# Sheet1.net
KiCad netlist of a schematic drawn in Altium Designer
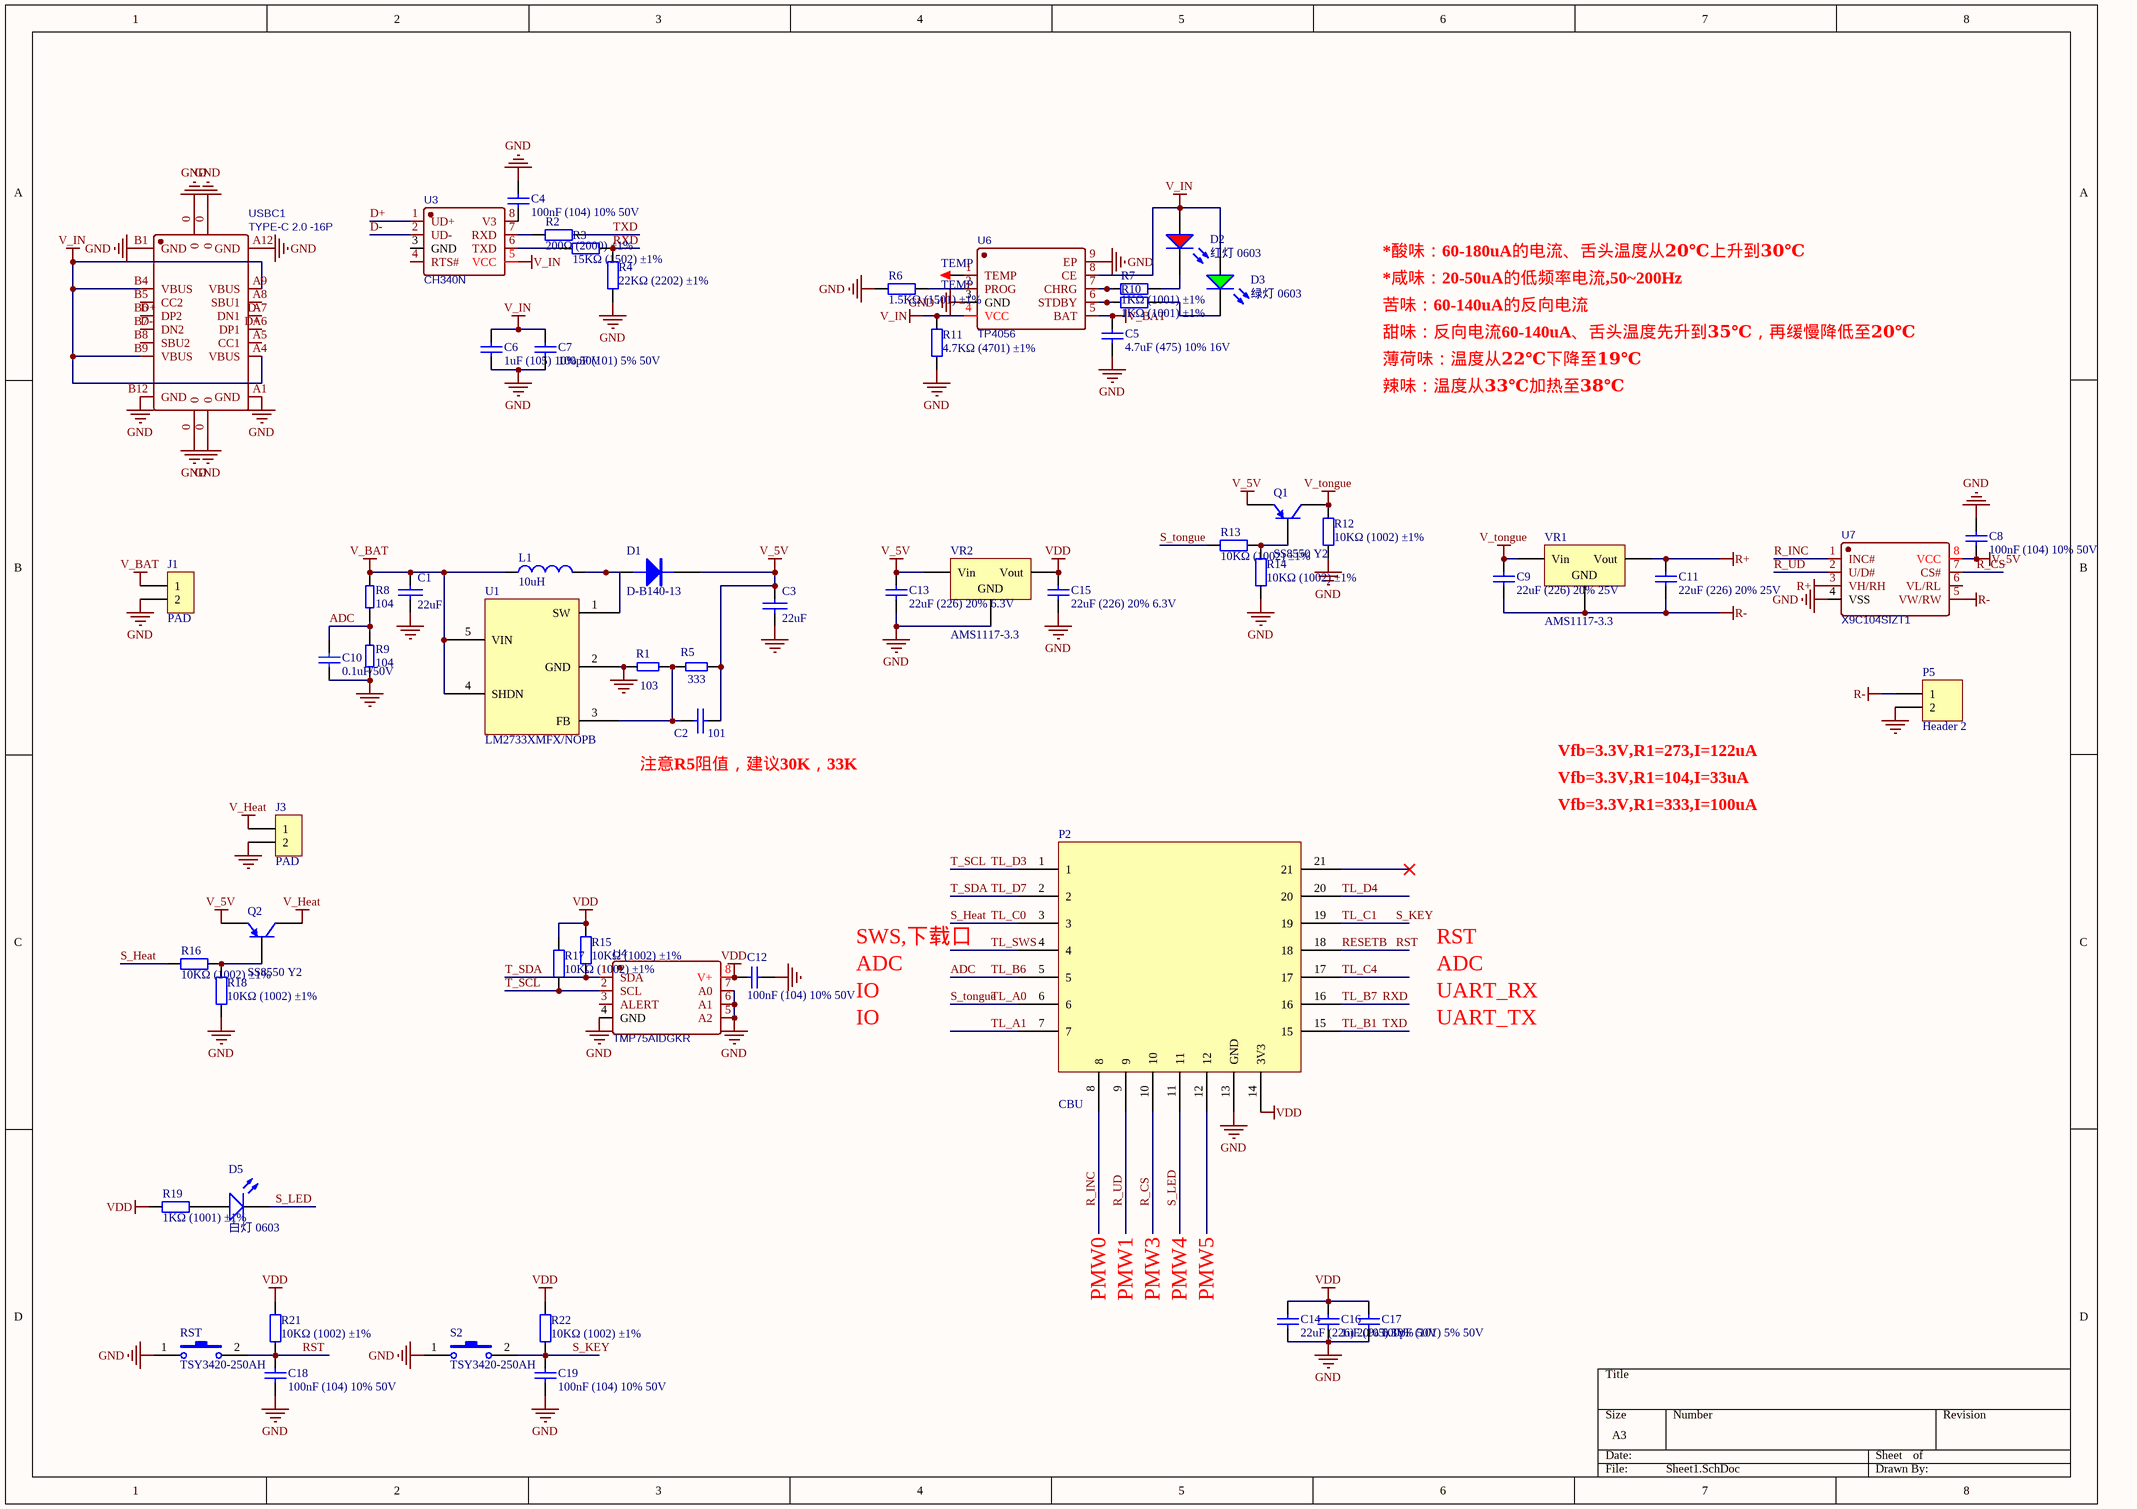
[diagram p0: Sheet1.SchDoc]

(export (version "E")
  (design (tool "Eeschema 10.0.6"))
  (components
    (comp (ref "C1") (value "22uF") (footprint "C1206") (libsource (lib "altium-import") (part "root_0_C1_")))
    (comp (ref "C2")
      (value "101")
      (footprint "C0603")
      (description "Capacitor")
      (libsource (lib "先锋器件封装库") (part "CAP"))
    )
    (comp (ref "C3") (value "22uF") (footprint "C1206") (libsource (lib "altium-import") (part "root_0_C1_")))
    (comp (ref "C4")
      (value "100nF (104) 10% 50V")
      (footprint "0603_C")
      (description "贴片电容")
      (libsource (lib "Miscellaneous Devices LC") (part "0603 100nF (104) 10% 50V"))
    )
    (comp (ref "C5")
      (value "4.7uF (475) 10% 16V")
      (footprint "0603_C")
      (description "贴片电容")
      (libsource (lib "Miscellaneous Devices LC") (part "0603 4.7uF (475) 10% 16V"))
    )
    (comp (ref "C6")
      (value "1uF (105) 10% 50V")
      (footprint "0603_C")
      (description "贴片电容")
      (libsource (lib "Miscellaneous Devices LC") (part "0603 1uF (105) 10% 50V"))
    )
    (comp (ref "C7")
      (value "100pF (101) 5% 50V")
      (footprint "0603_C")
      (description "贴片电容")
      (libsource (lib "Miscellaneous Devices LC") (part "0603 100pF (101) 5% 50V"))
    )
    (comp (ref "C8")
      (value "100nF (104) 10% 50V")
      (footprint "0603_C")
      (description "贴片电容")
      (libsource (lib "Miscellaneous Devices LC") (part "0603 100nF (104) 10% 50V"))
    )
    (comp (ref "C9")
      (value "22uF (226) 20% 25V")
      (footprint "0805_C")
      (description "贴片电容")
      (libsource (lib "Miscellaneous Devices LC") (part "0805 22uF (226) 20% 25V"))
    )
    (comp (ref "C10")
      (value "0.1uF/50V")
      (footprint "C0603_GRM18")
      (description "无极性电容")
      (fields (field (name "PART NUMBER") "1.02.05.00150") (field (name "修改人") "system"))
      (libsource (lib "Database_Libs") (part "Capacitor - non polarized"))
    )
    (comp (ref "C11")
      (value "22uF (226) 20% 25V")
      (footprint "0805_C")
      (description "贴片电容")
      (libsource (lib "Miscellaneous Devices LC") (part "0805 22uF (226) 20% 25V"))
    )
    (comp (ref "C12")
      (value "100nF (104) 10% 50V")
      (footprint "0603_C")
      (description "贴片电容")
      (libsource (lib "Miscellaneous Devices LC") (part "0603 100nF (104) 10% 50V"))
    )
    (comp (ref "C13")
      (value "22uF (226) 20% 6.3V")
      (footprint "0603_C")
      (description "贴片电容")
      (libsource (lib "Miscellaneous Devices LC") (part "0603 22uF (226) 20% 6.3V"))
    )
    (comp (ref "C14")
      (value "22uF (226) 20% 6.3V")
      (footprint "0603_C")
      (description "贴片电容")
      (libsource (lib "Miscellaneous Devices LC") (part "0603 22uF (226) 20% 6.3V"))
    )
    (comp (ref "C15")
      (value "22uF (226) 20% 6.3V")
      (footprint "0603_C")
      (description "贴片电容")
      (libsource (lib "Miscellaneous Devices LC") (part "0603 22uF (226) 20% 6.3V"))
    )
    (comp (ref "C16")
      (value "1uF (105) 10% 50V")
      (footprint "0603_C")
      (description "贴片电容")
      (libsource (lib "Miscellaneous Devices LC") (part "0603 1uF (105) 10% 50V"))
    )
    (comp (ref "C17")
      (value "100pF (101) 5% 50V")
      (footprint "0603_C")
      (description "贴片电容")
      (libsource (lib "Miscellaneous Devices LC") (part "0603 100pF (101) 5% 50V"))
    )
    (comp (ref "C18")
      (value "100nF (104) 10% 50V")
      (footprint "0603_C")
      (description "贴片电容")
      (libsource (lib "Miscellaneous Devices LC") (part "0603 100nF (104) 10% 50V"))
    )
    (comp (ref "C19")
      (value "100nF (104) 10% 50V")
      (footprint "0603_C")
      (description "贴片电容")
      (libsource (lib "Miscellaneous Devices LC") (part "0603 100nF (104) 10% 50V"))
    )
    (comp (ref "D1")
      (value "D-B140-13")
      (footprint "XF-SS12C")
      (description "Diode")
      (fields (field (name "SPECIFICATION") "D-B140-13"))
      (libsource (lib "先锋器件封装库") (part "DIODE"))
    )
    (comp (ref "D2")
      (value "红灯 0603")
      (footprint "0603_LED_S1")
      (description "发光二极管")
      (libsource (lib "LED") (part "0603 红灯"))
    )
    (comp (ref "D3")
      (value "绿灯 0603")
      (footprint "0603_LED_S1")
      (description "发光二极管")
      (libsource (lib "LED") (part "0603 绿灯"))
    )
    (comp (ref "D5")
      (value "白灯 0603")
      (footprint "0603_LED_S1")
      (description "发光二极管")
      (libsource (lib "LED") (part "0603 白灯"))
    )
    (comp (ref "J1")
      (value "PAD")
      (footprint "POW_5#")
      (description "Connector")
      (libsource (lib "altium-import") (part "root_0_CON2_"))
    )
    (comp (ref "J3")
      (value "PAD")
      (footprint "HDR1X2")
      (description "Connector")
      (libsource (lib "接插件") (part "CON2"))
    )
    (comp (ref "L1")
      (value "10uH")
      (footprint "CD73")
      (description "Inductor")
      (fields (field (name "Comment") "4.7uH") (field (name "PUBLISHER") "Altium Limited"))
      (libsource (lib "altium-import") (part "root_0_Inductor_"))
    )
    (comp (ref "P2")
      (value "CBU")
      (footprint "CBU-PCBA")
      (fields (field (name "PART NUMBER") "0110"))
      (libsource (lib "Database_Libs1") (part "CBU"))
    )
    (comp (ref "P5")
      (value "Header 2")
      (footprint "HDR1X2")
      (description "Header, 2-Pin")
      (fields (field (name "PUBLISHER") "Altium Limited"))
      (libsource (lib "Miscellaneous Connectors") (part "Header 2"))
    )
    (comp (ref "Q1")
      (value "SS8550 Y2")
      (footprint "SOT-23(SOT-23-3)")
      (description "三极管")
      (libsource (lib "Transistor_PNP") (part "SOT-23 SS8550 Y2"))
    )
    (comp (ref "Q2")
      (value "SS8550 Y2")
      (footprint "SOT-23(SOT-23-3)")
      (description "三极管")
      (libsource (lib "Transistor_PNP") (part "SOT-23 SS8550 Y2"))
    )
    (comp (ref "R1")
      (value "103")
      (footprint "R0603")
      (description "RES")
      (libsource (lib "先锋器件封装库") (part "RES-1"))
    )
    (comp (ref "R2")
      (value "200Ω (2000) ±1%")
      (footprint "0603_R")
      (description "贴片电阻")
      (libsource (lib "Miscellaneous Devices LC") (part "0603 200Ω (2000) 1%"))
    )
    (comp (ref "R3")
      (value "15KΩ (1502) ±1%")
      (footprint "0603_R")
      (description "贴片电阻")
      (libsource (lib "Miscellaneous Devices LC") (part "0603 15KΩ (1502) 1%"))
    )
    (comp (ref "R4")
      (value "22KΩ (2202) ±1%")
      (footprint "0603_R")
      (description "贴片电阻")
      (libsource (lib "Miscellaneous Devices LC") (part "0603 22KΩ (2202) 1%"))
    )
    (comp (ref "R5")
      (value "333")
      (footprint "R0603")
      (description "RES")
      (libsource (lib "先锋器件封装库") (part "RES-1"))
    )
    (comp (ref "R6")
      (value "1.5KΩ (1501) ±1%")
      (footprint "0603_R")
      (description "贴片电阻")
      (libsource (lib "Miscellaneous Devices LC") (part "0603 1.5KΩ (1501) 1%"))
    )
    (comp (ref "R7")
      (value "1KΩ (1001) ±1%")
      (footprint "0603_R")
      (description "贴片电阻")
      (libsource (lib "Miscellaneous Devices LC") (part "0603 1KΩ (1001) 1%"))
    )
    (comp (ref "R8")
      (value "104")
      (footprint "R0603")
      (description "RES")
      (libsource (lib "先锋器件封装库") (part "RES-1"))
    )
    (comp (ref "R9")
      (value "104")
      (footprint "R0603")
      (description "RES")
      (libsource (lib "先锋器件封装库") (part "RES-1"))
    )
    (comp (ref "R10")
      (value "1KΩ (1001) ±1%")
      (footprint "0603_R")
      (description "贴片电阻")
      (libsource (lib "Miscellaneous Devices LC") (part "0603 1KΩ (1001) 1%"))
    )
    (comp (ref "R11")
      (value "4.7KΩ (4701) ±1%")
      (footprint "0603_R")
      (description "贴片电阻")
      (libsource (lib "Miscellaneous Devices LC") (part "0603 4.7KΩ (4701) 1%"))
    )
    (comp (ref "R12")
      (value "10KΩ (1002) ±1%")
      (footprint "0603_R")
      (description "贴片电阻")
      (libsource (lib "Miscellaneous Devices LC") (part "0603 10KΩ (1002) 1%"))
    )
    (comp (ref "R13")
      (value "10KΩ (1002) ±1%")
      (footprint "0603_R")
      (description "贴片电阻")
      (libsource (lib "") (part "0603 10KΩ (1002) 1%_3"))
    )
    (comp (ref "R14")
      (value "10KΩ (1002) ±1%")
      (footprint "0603_R")
      (description "贴片电阻")
      (libsource (lib "") (part "0603 10KΩ (1002) 1%_2"))
    )
    (comp (ref "R15")
      (value "10KΩ (1002) ±1%")
      (footprint "0603_R")
      (description "贴片电阻")
      (libsource (lib "Miscellaneous Devices LC") (part "0603 10KΩ (1002) 1%"))
    )
    (comp (ref "R16")
      (value "10KΩ (1002) ±1%")
      (footprint "0603_R")
      (description "贴片电阻")
      (libsource (lib "") (part "0603 10KΩ (1002) 1%_1"))
    )
    (comp (ref "R17")
      (value "10KΩ (1002) ±1%")
      (footprint "0603_R")
      (description "贴片电阻")
      (libsource (lib "Miscellaneous Devices LC") (part "0603 10KΩ (1002) 1%"))
    )
    (comp (ref "R18")
      (value "10KΩ (1002) ±1%")
      (footprint "0603_R")
      (description "贴片电阻")
      (libsource (lib "Miscellaneous Devices LC") (part "0603 10KΩ (1002) 1%"))
    )
    (comp (ref "R19")
      (value "1KΩ (1001) ±1%")
      (footprint "0603_R")
      (description "贴片电阻")
      (libsource (lib "Miscellaneous Devices LC") (part "0603 1KΩ (1001) 1%"))
    )
    (comp (ref "R21")
      (value "10KΩ (1002) ±1%")
      (footprint "0603_R")
      (description "贴片电阻")
      (libsource (lib "Miscellaneous Devices LC") (part "0603 10KΩ (1002) 1%"))
    )
    (comp (ref "R22")
      (value "10KΩ (1002) ±1%")
      (footprint "0603_R")
      (description "贴片电阻")
      (libsource (lib "Miscellaneous Devices LC") (part "0603 10KΩ (1002) 1%"))
    )
    (comp (ref "RST")
      (value "TSY3420-250AH")
      (footprint "TSW SMD-3*6*4.3")
      (description "2pin轻触开关（无固定脚）")
      (fields (field (name "PART NUMBER") "1.13.04.00024") (field (name "修改人") "system"))
      (libsource (lib "Database_Libs") (part "SW-PB2"))
    )
    (comp (ref "S2")
      (value "TSY3420-250AH")
      (footprint "TSW SMD-3*6*4.3")
      (description "2pin轻触开关（无固定脚）")
      (fields (field (name "PART NUMBER") "1.13.04.00024") (field (name "修改人") "system"))
      (libsource (lib "Database_Libs") (part "SW-PB2"))
    )
    (comp (ref "TEMP")
      (value "TEMP")
      (footprint "TEST 1")
      (description "测试点")
      (libsource (lib "0.7 - 常用按键-开关-蜂鸣器-电池") (part "TEST"))
    )
    (comp (ref "U1")
      (value "LM2733XMFX/NOPB")
      (footprint "SOT23-5")
      (description "LM2733")
      (fields (field (name "SPECIFICATION") "LM2733XMFX/NOPB"))
      (libsource (lib "先锋器件封装库") (part "LM2733"))
    )
    (comp (ref "U3")
      (value "CH340N")
      (footprint "SOP-8")
      (fields (field (name "BOM_SUPPLIER PART") "C506813") (field (name "CONTRIBUTOR") "LCSC"))
      (libsource (lib "TY") (part "CH340N"))
    )
    (comp (ref "U4")
      (value "TMP75AIDGKR")
      (footprint "VSSOP-8_L3.0-W3.0-P0.65-LS5.0-BL")
      (fields (field (name "BOM_SUPPLIER PART") "C105258") (field (name "CONTRIBUTOR") "LCSC"))
      (libsource (lib "TY") (part "TMP75AIDGKR"))
    )
    (comp (ref "U6")
      (value "TP4056")
      (footprint "ESOP8_N")
      (fields (field (name "BOM_SUPPLIER PART") "C725790") (field (name "CONTRIBUTOR") "LCSC"))
      (libsource (lib "TY") (part "TP4056_C725790"))
    )
    (comp (ref "U7")
      (value "X9C104SIZT1")
      (footprint "SOIC-8")
      (fields (field (name "BOM_SUPPLIER PART") "C11979"))
      (libsource (lib "TY") (part "X9C104SIZT1"))
    )
    (comp (ref "USBC1")
      (value "TYPE-C 2.0 -16P")
      (footprint "USB-C-SMD_TYPE-C-USB-5")
      (description "USB2.0 Type-C 母座 16Pin")
      (libsource (lib "0.8 - 以太网-音频-USB插座") (part "USB2.0 Type-C 16Pin母座"))
    )
    (comp (ref "VR1")
      (value "AMS1117-3.3")
      (footprint "SOT-223")
      (description "低压差线性稳压(LDO)")
      (libsource (lib "LDO") (part "SOT-223 AMS1117-3.3"))
    )
    (comp (ref "VR2")
      (value "AMS1117-3.3")
      (footprint "SOT-223")
      (description "低压差线性稳压(LDO)")
      (libsource (lib "LDO") (part "SOT-223 AMS1117-3.3"))
    )
  )
  (nets
    (net (code "1") (name "/ADC") (class "Default")
      (node (ref "C10") (pin "2") (pinfunction "2_2") (pintype "passive"))
      (node (ref "P2") (pin "5") (pinfunction "5_5") (pintype "passive"))
      (node (ref "R8") (pin "1") (pintype "passive"))
      (node (ref "R9") (pin "2") (pintype "passive"))
    )
    (net (code "2") (name "/D+") (class "Default")
      (node (ref "U3") (pin "1") (pinfunction "UD+_1") (pintype "passive"))
      (node (ref "USBC1") (pin "A6") (pinfunction "DP1_A6") (pintype "passive"))
      (node (ref "USBC1") (pin "B6") (pinfunction "DP2_B6") (pintype "passive"))
    )
    (net (code "3") (name "/D-") (class "Default")
      (node (ref "U3") (pin "2") (pinfunction "UD-_2") (pintype "passive"))
      (node (ref "USBC1") (pin "A7") (pinfunction "DN1_A7") (pintype "passive"))
      (node (ref "USBC1") (pin "B7") (pinfunction "DN2_B7") (pintype "passive"))
    )
    (net (code "4") (name "/RESETB") (class "Default")
      (node (ref "C18") (pin "2") (pinfunction "2_2") (pintype "passive"))
      (node (ref "P2") (pin "18") (pinfunction "18_18") (pintype "passive"))
      (node (ref "R21") (pin "1") (pinfunction "1_1") (pintype "passive"))
      (node (ref "RST") (pin "2") (pinfunction "2_2") (pintype "passive"))
    )
    (net (code "5") (name "/RXD") (class "Default")
      (node (ref "P2") (pin "16") (pinfunction "16_16") (pintype "passive"))
      (node (ref "R3") (pin "2") (pinfunction "2_2") (pintype "passive"))
      (node (ref "R4") (pin "2") (pinfunction "2_2") (pintype "passive"))
    )
    (net (code "6") (name "/R_CS") (class "Default")
      (node (ref "P2") (pin "10") (pinfunction "10_10") (pintype "passive"))
      (node (ref "U7") (pin "7") (pinfunction "CS#_7") (pintype "passive"))
    )
    (net (code "7") (name "/R_INC") (class "Default")
      (node (ref "P2") (pin "8") (pinfunction "8_8") (pintype "passive"))
      (node (ref "U7") (pin "1") (pinfunction "INC#_1") (pintype "passive"))
    )
    (net (code "8") (name "/R_UD") (class "Default")
      (node (ref "P2") (pin "9") (pinfunction "9_9") (pintype "passive"))
      (node (ref "U7") (pin "2") (pinfunction "U/D#_2") (pintype "passive"))
    )
    (net (code "9") (name "/S_Heat") (class "Default")
      (node (ref "P2") (pin "3") (pinfunction "3_3") (pintype "passive"))
      (node (ref "R16") (pin "1") (pinfunction "1_1") (pintype "passive"))
    )
    (net (code "10") (name "/S_KEY") (class "Default")
      (node (ref "C19") (pin "2") (pinfunction "2_2") (pintype "passive"))
      (node (ref "P2") (pin "19") (pinfunction "19_19") (pintype "passive"))
      (node (ref "R22") (pin "1") (pinfunction "1_1") (pintype "passive"))
      (node (ref "S2") (pin "2") (pinfunction "2_2") (pintype "passive"))
    )
    (net (code "11") (name "/S_LED") (class "Default")
      (node (ref "D5") (pin "K") (pinfunction "K_K") (pintype "passive"))
      (node (ref "P2") (pin "11") (pinfunction "11_11") (pintype "passive"))
    )
    (net (code "12") (name "/S_tongue") (class "Default")
      (node (ref "P2") (pin "6") (pinfunction "6_6") (pintype "passive"))
      (node (ref "R13") (pin "2") (pinfunction "2_2") (pintype "passive"))
    )
    (net (code "13") (name "/TL_A1") (class "Default")
      (node (ref "P2") (pin "7") (pinfunction "7_7") (pintype "passive"))
    )
    (net (code "14") (name "/TL_B1") (class "Default")
      (node (ref "P2") (pin "15") (pinfunction "15_15") (pintype "passive"))
      (node (ref "R2") (pin "2") (pinfunction "2_2") (pintype "passive"))
    )
    (net (code "15") (name "/TL_C4") (class "Default")
      (node (ref "P2") (pin "17") (pinfunction "17_17") (pintype "passive"))
    )
    (net (code "16") (name "/TL_D3") (class "Default")
      (node (ref "P2") (pin "1") (pinfunction "1_1") (pintype "passive"))
      (node (ref "R17") (pin "1") (pinfunction "1_1") (pintype "passive"))
      (node (ref "U4") (pin "2") (pinfunction "SCL_2") (pintype "passive"))
    )
    (net (code "17") (name "/TL_D4") (class "Default")
      (node (ref "P2") (pin "20") (pinfunction "20_20") (pintype "passive"))
    )
    (net (code "18") (name "/TL_D7") (class "Default")
      (node (ref "P2") (pin "2") (pinfunction "2_2") (pintype "passive"))
      (node (ref "R15") (pin "1") (pinfunction "1_1") (pintype "passive"))
      (node (ref "U4") (pin "1") (pinfunction "SDA_1") (pintype "passive"))
    )
    (net (code "19") (name "/TL_SWS") (class "Default")
      (node (ref "P2") (pin "4") (pinfunction "4_4") (pintype "passive"))
    )
    (net (code "20") (name "GND") (class "Default")
      (node (ref "C1") (pin "2") (pinfunction "2_2") (pintype "passive"))
      (node (ref "C10") (pin "1") (pinfunction "1_1") (pintype "passive"))
      (node (ref "C12") (pin "2") (pinfunction "2_2") (pintype "passive"))
      (node (ref "C13") (pin "1") (pinfunction "1_1") (pintype "passive"))
      (node (ref "C14") (pin "1") (pinfunction "1_1") (pintype "passive"))
      (node (ref "C15") (pin "1") (pinfunction "1_1") (pintype "passive"))
      (node (ref "C16") (pin "1") (pinfunction "1_1") (pintype "passive"))
      (node (ref "C17") (pin "1") (pinfunction "1_1") (pintype "passive"))
      (node (ref "C18") (pin "1") (pinfunction "1_1") (pintype "passive"))
      (node (ref "C19") (pin "1") (pinfunction "1_1") (pintype "passive"))
      (node (ref "C3") (pin "2") (pinfunction "2_2") (pintype "passive"))
      (node (ref "C4") (pin "2") (pinfunction "2_2") (pintype "passive"))
      (node (ref "C5") (pin "1") (pinfunction "1_1") (pintype "passive"))
      (node (ref "C6") (pin "1") (pinfunction "1_1") (pintype "passive"))
      (node (ref "C7") (pin "1") (pinfunction "1_1") (pintype "passive"))
      (node (ref "C8") (pin "2") (pinfunction "2_2") (pintype "passive"))
      (node (ref "J1") (pin "2") (pinfunction "2_2") (pintype "passive"))
      (node (ref "J3") (pin "2") (pinfunction "2_2") (pintype "passive"))
      (node (ref "P2") (pin "13") (pinfunction "GND_13") (pintype "passive"))
      (node (ref "P5") (pin "2") (pinfunction "2_2") (pintype "passive"))
      (node (ref "R1") (pin "1") (pintype "passive"))
      (node (ref "R11") (pin "1") (pinfunction "1_1") (pintype "passive"))
      (node (ref "R12") (pin "1") (pinfunction "1_1") (pintype "passive"))
      (node (ref "R14") (pin "2") (pinfunction "2_2") (pintype "passive"))
      (node (ref "R18") (pin "1") (pinfunction "1_1") (pintype "passive"))
      (node (ref "R4") (pin "1") (pinfunction "1_1") (pintype "passive"))
      (node (ref "R6") (pin "1") (pinfunction "1_1") (pintype "passive"))
      (node (ref "R9") (pin "1") (pintype "passive"))
      (node (ref "RST") (pin "1") (pinfunction "1_1") (pintype "passive"))
      (node (ref "S2") (pin "1") (pinfunction "1_1") (pintype "passive"))
      (node (ref "U1") (pin "2") (pinfunction "GND_2") (pintype "passive"))
      (node (ref "U4") (pin "4") (pinfunction "GND_4") (pintype "passive"))
      (node (ref "U4") (pin "5") (pinfunction "A2_5") (pintype "passive"))
      (node (ref "U4") (pin "6") (pinfunction "A1_6") (pintype "passive"))
      (node (ref "U4") (pin "7") (pinfunction "A0_7") (pintype "passive"))
      (node (ref "U6") (pin "3") (pinfunction "GND_3") (pintype "passive"))
      (node (ref "U6") (pin "9") (pinfunction "EP_9") (pintype "passive"))
      (node (ref "U7") (pin "4") (pinfunction "VSS_4") (pintype "passive"))
      (node (ref "USBC1") (pin "0") (pinfunction "0_0") (pintype "passive"))
      (node (ref "USBC1") (pin "A1") (pinfunction "GND_A1") (pintype "passive"))
      (node (ref "USBC1") (pin "A12") (pinfunction "GND_A12") (pintype "passive"))
      (node (ref "USBC1") (pin "B1") (pinfunction "GND_B1") (pintype "passive"))
      (node (ref "USBC1") (pin "B12") (pinfunction "GND_B12") (pintype "passive"))
      (node (ref "VR2") (pin "1") (pinfunction "GND_1") (pintype "passive"))
    )
    (net (code "21") (name "Net-(D2-PadK)") (class "Default")
      (node (ref "D2") (pin "K") (pinfunction "K_K") (pintype "passive"))
      (node (ref "R7") (pin "2") (pinfunction "2_2") (pintype "passive"))
    )
    (net (code "22") (name "Net-(D3-PadK)") (class "Default")
      (node (ref "D3") (pin "K") (pinfunction "K_K") (pintype "passive"))
      (node (ref "R10") (pin "2") (pinfunction "2_2") (pintype "passive"))
    )
    (net (code "23") (name "Net-(D5-PadA)") (class "Default")
      (node (ref "D5") (pin "A") (pinfunction "A_A") (pintype "passive"))
      (node (ref "R19") (pin "2") (pinfunction "2_2") (pintype "passive"))
    )
    (net (code "24") (name "Net-(Q1-B)") (class "Default")
      (node (ref "Q1") (pin "1") (pinfunction "B_1") (pintype "passive"))
      (node (ref "R13") (pin "1") (pinfunction "1_1") (pintype "passive"))
      (node (ref "R14") (pin "1") (pinfunction "1_1") (pintype "passive"))
    )
    (net (code "25") (name "Net-(Q2-B)") (class "Default")
      (node (ref "Q2") (pin "1") (pinfunction "B_1") (pintype "passive"))
      (node (ref "R16") (pin "2") (pinfunction "2_2") (pintype "passive"))
      (node (ref "R18") (pin "2") (pinfunction "2_2") (pintype "passive"))
    )
    (net (code "26") (name "Net-(U1-FB)") (class "Default")
      (node (ref "C2") (pin "2") (pinfunction "2_2") (pintype "passive"))
      (node (ref "R1") (pin "2") (pintype "passive"))
      (node (ref "R5") (pin "2") (pintype "passive"))
      (node (ref "U1") (pin "3") (pinfunction "FB_3") (pintype "passive"))
    )
    (net (code "27") (name "Net-(U1-SW)") (class "Default")
      (node (ref "D1") (pin "A") (pinfunction "A_A") (pintype "passive"))
      (node (ref "L1") (pin "2") (pinfunction "2_2") (pintype "passive"))
      (node (ref "U1") (pin "1") (pinfunction "SW_1") (pintype "passive"))
    )
    (net (code "28") (name "Net-(U3-RXD)") (class "Default")
      (node (ref "R2") (pin "1") (pinfunction "1_1") (pintype "passive"))
      (node (ref "U3") (pin "7") (pinfunction "RXD_7") (pintype "passive"))
    )
    (net (code "29") (name "Net-(U3-TXD)") (class "Default")
      (node (ref "R3") (pin "1") (pinfunction "1_1") (pintype "passive"))
      (node (ref "U3") (pin "6") (pinfunction "TXD_6") (pintype "passive"))
    )
    (net (code "30") (name "Net-(U3-V3)") (class "Default")
      (node (ref "C4") (pin "1") (pinfunction "1_1") (pintype "passive"))
      (node (ref "U3") (pin "8") (pinfunction "V3_8") (pintype "passive"))
    )
    (net (code "31") (name "Net-(U6-CHRG)") (class "Default")
      (node (ref "R7") (pin "1") (pinfunction "1_1") (pintype "passive"))
      (node (ref "U6") (pin "7") (pinfunction "CHRG_7") (pintype "passive"))
    )
    (net (code "32") (name "Net-(U6-PROG)") (class "Default")
      (node (ref "R6") (pin "2") (pinfunction "2_2") (pintype "passive"))
      (node (ref "U6") (pin "2") (pinfunction "PROG_2") (pintype "passive"))
    )
    (net (code "33") (name "Net-(U6-STDBY)") (class "Default")
      (node (ref "R10") (pin "1") (pinfunction "1_1") (pintype "passive"))
      (node (ref "U6") (pin "6") (pinfunction "STDBY_6") (pintype "passive"))
    )
    (net (code "34") (name "Net-(U6-TEMP)") (class "Default")
      (node (ref "TEMP") (pin "1") (pinfunction "1_1") (pintype "passive"))
      (node (ref "U6") (pin "1") (pinfunction "TEMP_1") (pintype "passive"))
    )
    (net (code "35") (name "R+") (class "Default")
      (node (ref "C11") (pin "2") (pinfunction "2_2") (pintype "passive"))
      (node (ref "U7") (pin "3") (pinfunction "VH/RH_3") (pintype "passive"))
      (node (ref "VR1") (pin "2") (pinfunction "Vout_2") (pintype "passive"))
    )
    (net (code "36") (name "R-") (class "Default")
      (node (ref "C11") (pin "1") (pinfunction "1_1") (pintype "passive"))
      (node (ref "C9") (pin "1") (pinfunction "1_1") (pintype "passive"))
      (node (ref "P5") (pin "1") (pinfunction "1_1") (pintype "passive"))
      (node (ref "U7") (pin "5") (pinfunction "VW/RW_5") (pintype "passive"))
      (node (ref "VR1") (pin "1") (pinfunction "GND_1") (pintype "passive"))
    )
    (net (code "37") (name "VDD") (class "Default")
      (node (ref "C12") (pin "1") (pinfunction "1_1") (pintype "passive"))
      (node (ref "C14") (pin "2") (pinfunction "2_2") (pintype "passive"))
      (node (ref "C15") (pin "2") (pinfunction "2_2") (pintype "passive"))
      (node (ref "C16") (pin "2") (pinfunction "2_2") (pintype "passive"))
      (node (ref "C17") (pin "2") (pinfunction "2_2") (pintype "passive"))
      (node (ref "P2") (pin "14") (pinfunction "3V3_14") (pintype "passive"))
      (node (ref "R15") (pin "2") (pinfunction "2_2") (pintype "passive"))
      (node (ref "R17") (pin "2") (pinfunction "2_2") (pintype "passive"))
      (node (ref "R19") (pin "1") (pinfunction "1_1") (pintype "passive"))
      (node (ref "R21") (pin "2") (pinfunction "2_2") (pintype "passive"))
      (node (ref "R22") (pin "2") (pinfunction "2_2") (pintype "passive"))
      (node (ref "U4") (pin "8") (pinfunction "V+_8") (pintype "passive"))
      (node (ref "VR2") (pin "2") (pinfunction "Vout_2") (pintype "passive"))
    )
    (net (code "38") (name "V_5V") (class "Default")
      (node (ref "C13") (pin "2") (pinfunction "2_2") (pintype "passive"))
      (node (ref "C2") (pin "1") (pinfunction "1_1") (pintype "passive"))
      (node (ref "C3") (pin "1") (pinfunction "1_1") (pintype "passive"))
      (node (ref "C8") (pin "1") (pinfunction "1_1") (pintype "passive"))
      (node (ref "D1") (pin "K") (pinfunction "K_K") (pintype "passive"))
      (node (ref "Q1") (pin "2") (pinfunction "E_2") (pintype "passive"))
      (node (ref "Q2") (pin "2") (pinfunction "E_2") (pintype "passive"))
      (node (ref "R5") (pin "1") (pintype "passive"))
      (node (ref "U7") (pin "8") (pinfunction "VCC_8") (pintype "passive"))
      (node (ref "VR2") (pin "3") (pinfunction "Vin_3") (pintype "passive"))
    )
    (net (code "39") (name "V_BAT") (class "Default")
      (node (ref "C1") (pin "1") (pinfunction "1_1") (pintype "passive"))
      (node (ref "C5") (pin "2") (pinfunction "2_2") (pintype "passive"))
      (node (ref "J1") (pin "1") (pinfunction "1_1") (pintype "passive"))
      (node (ref "L1") (pin "1") (pinfunction "1_1") (pintype "passive"))
      (node (ref "R8") (pin "2") (pintype "passive"))
      (node (ref "U1") (pin "4") (pinfunction "SHDN_4") (pintype "passive"))
      (node (ref "U1") (pin "5") (pinfunction "VIN_5") (pintype "passive"))
      (node (ref "U6") (pin "5") (pinfunction "BAT_5") (pintype "passive"))
    )
    (net (code "40") (name "V_Heat") (class "Default")
      (node (ref "J3") (pin "1") (pinfunction "1_1") (pintype "passive"))
      (node (ref "Q2") (pin "3") (pinfunction "C_3") (pintype "passive"))
    )
    (net (code "41") (name "V_IN") (class "Default")
      (node (ref "C6") (pin "2") (pinfunction "2_2") (pintype "passive"))
      (node (ref "C7") (pin "2") (pinfunction "2_2") (pintype "passive"))
      (node (ref "D2") (pin "A") (pinfunction "A_A") (pintype "passive"))
      (node (ref "D3") (pin "A") (pinfunction "A_A") (pintype "passive"))
      (node (ref "R11") (pin "2") (pinfunction "2_2") (pintype "passive"))
      (node (ref "U3") (pin "5") (pinfunction "VCC_5") (pintype "passive"))
      (node (ref "U6") (pin "4") (pinfunction "VCC_4") (pintype "passive"))
      (node (ref "U6") (pin "8") (pinfunction "CE_8") (pintype "passive"))
      (node (ref "USBC1") (pin "A4") (pinfunction "VBUS_A4") (pintype "passive"))
      (node (ref "USBC1") (pin "A9") (pinfunction "VBUS_A9") (pintype "passive"))
      (node (ref "USBC1") (pin "B4") (pinfunction "VBUS_B4") (pintype "passive"))
      (node (ref "USBC1") (pin "B9") (pinfunction "VBUS_B9") (pintype "passive"))
    )
    (net (code "42") (name "V_tongue") (class "Default")
      (node (ref "C9") (pin "2") (pinfunction "2_2") (pintype "passive"))
      (node (ref "Q1") (pin "3") (pinfunction "C_3") (pintype "passive"))
      (node (ref "R12") (pin "2") (pinfunction "2_2") (pintype "passive"))
      (node (ref "VR1") (pin "3") (pinfunction "Vin_3") (pintype "passive"))
    )
    (net (code "43") (name "unconnected-(P2-Pad12)") (class "Default")
      (node (ref "P2") (pin "12") (pinfunction "12_12") (pintype "passive"))
    )
    (net (code "44") (name "unconnected-(P2-Pad21)") (class "Default")
      (node (ref "P2") (pin "21") (pinfunction "21_21") (pintype "passive+no_connect"))
    )
    (net (code "45") (name "unconnected-(U3-GND-Pad3)") (class "Default")
      (node (ref "U3") (pin "3") (pinfunction "GND_3") (pintype "passive"))
    )
    (net (code "46") (name "unconnected-(U3-RTS#-Pad4)") (class "Default")
      (node (ref "U3") (pin "4") (pinfunction "RTS#_4") (pintype "passive"))
    )
    (net (code "47") (name "unconnected-(U4-ALERT-Pad3)") (class "Default")
      (node (ref "U4") (pin "3") (pinfunction "ALERT_3") (pintype "passive"))
    )
    (net (code "48") (name "unconnected-(U7-VL{slash}RL-Pad6)") (class "Default")
      (node (ref "U7") (pin "6") (pinfunction "VL/RL_6") (pintype "passive"))
    )
    (net (code "49") (name "unconnected-(USBC1-CC1-PadA5)") (class "Default")
      (node (ref "USBC1") (pin "A5") (pinfunction "CC1_A5") (pintype "passive"))
    )
    (net (code "50") (name "unconnected-(USBC1-CC2-PadB5)") (class "Default")
      (node (ref "USBC1") (pin "B5") (pinfunction "CC2_B5") (pintype "passive"))
    )
    (net (code "51") (name "unconnected-(USBC1-SBU1-PadA8)") (class "Default")
      (node (ref "USBC1") (pin "A8") (pinfunction "SBU1_A8") (pintype "passive"))
    )
    (net (code "52") (name "unconnected-(USBC1-SBU2-PadB8)") (class "Default")
      (node (ref "USBC1") (pin "B8") (pinfunction "SBU2_B8") (pintype "passive"))
    )
  )
)
